# 5V_to_15V.net
KiCad netlist of a schematic drawn in Altium Designer
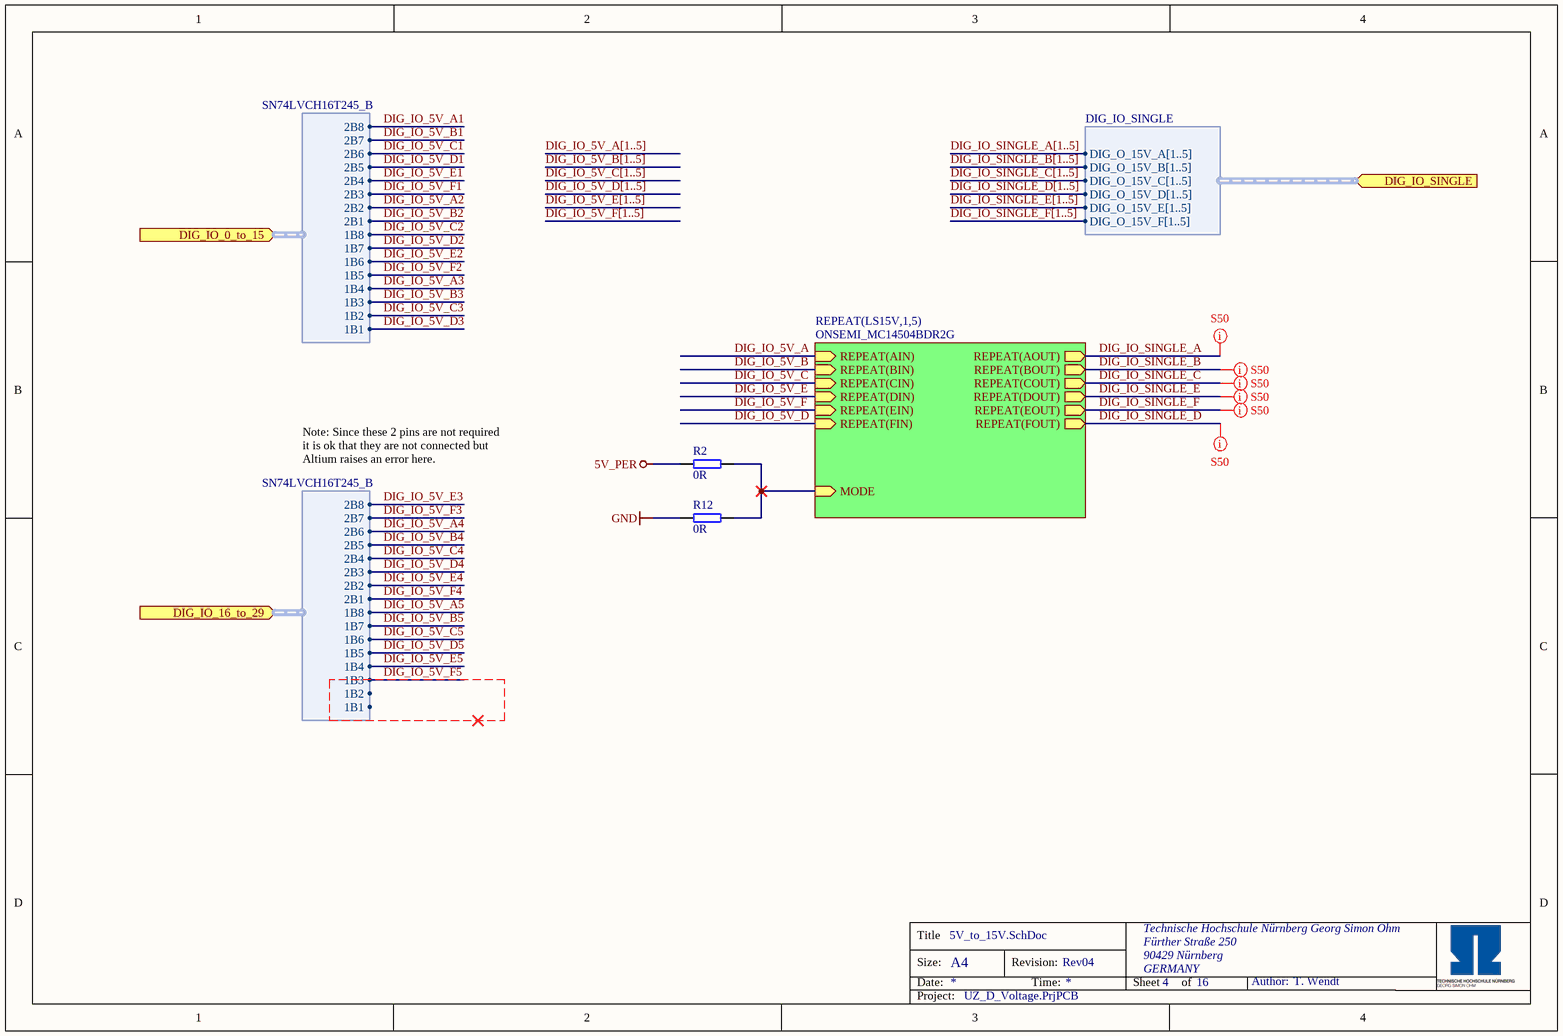
[diagram p0: 5V_to_15V.SchDoc]

(export (version "E")
  (design (tool "Eeschema 10.0.6"))
  (components
    (comp (ref "R2")
      (value "0R")
      (footprint "RES 0603_1608")
      (description "SMD resistor E24 series")
      (fields
        (field (name "MANUFACTURER PART NUMBER") "RC0603JR-070RL")
        (field (name "MANUFACTURER") "YAGEO")
        (field (name "CREATED FROM") "MGremer")
      )
      (libsource (lib "user") (part "Resistor"))
    )
    (comp (ref "R12")
      (value "0R")
      (footprint "RES 0603_1608")
      (description "SMD resistor E24 series")
      (fields
        (field (name "MANUFACTURER PART NUMBER") "RC0603JR-070RL")
        (field (name "MANUFACTURER") "YAGEO")
        (field (name "CREATED FROM") "MGremer")
      )
      (libsource (lib "user") (part "Resistor"))
    )
  )
  (nets
    (net (code "87") (name "/MODE") (class "Default")
      (node (ref "R12") (pin "2") (pinfunction "2_2") (pintype "passive"))
      (node (ref "R2") (pin "2") (pinfunction "2_2") (pintype "passive"))
    )
    (net (code "90") (name "5V_PER") (class "Default")
      (node (ref "R2") (pin "1") (pinfunction "1_1") (pintype "passive"))
    )
    (net (code "91") (name "GND") (class "Default")
      (node (ref "R12") (pin "1") (pinfunction "1_1") (pintype "passive"))
    )
  )
)
